# connections_to_beaglebone.net
KiCad netlist of a schematic drawn in Altium Designer
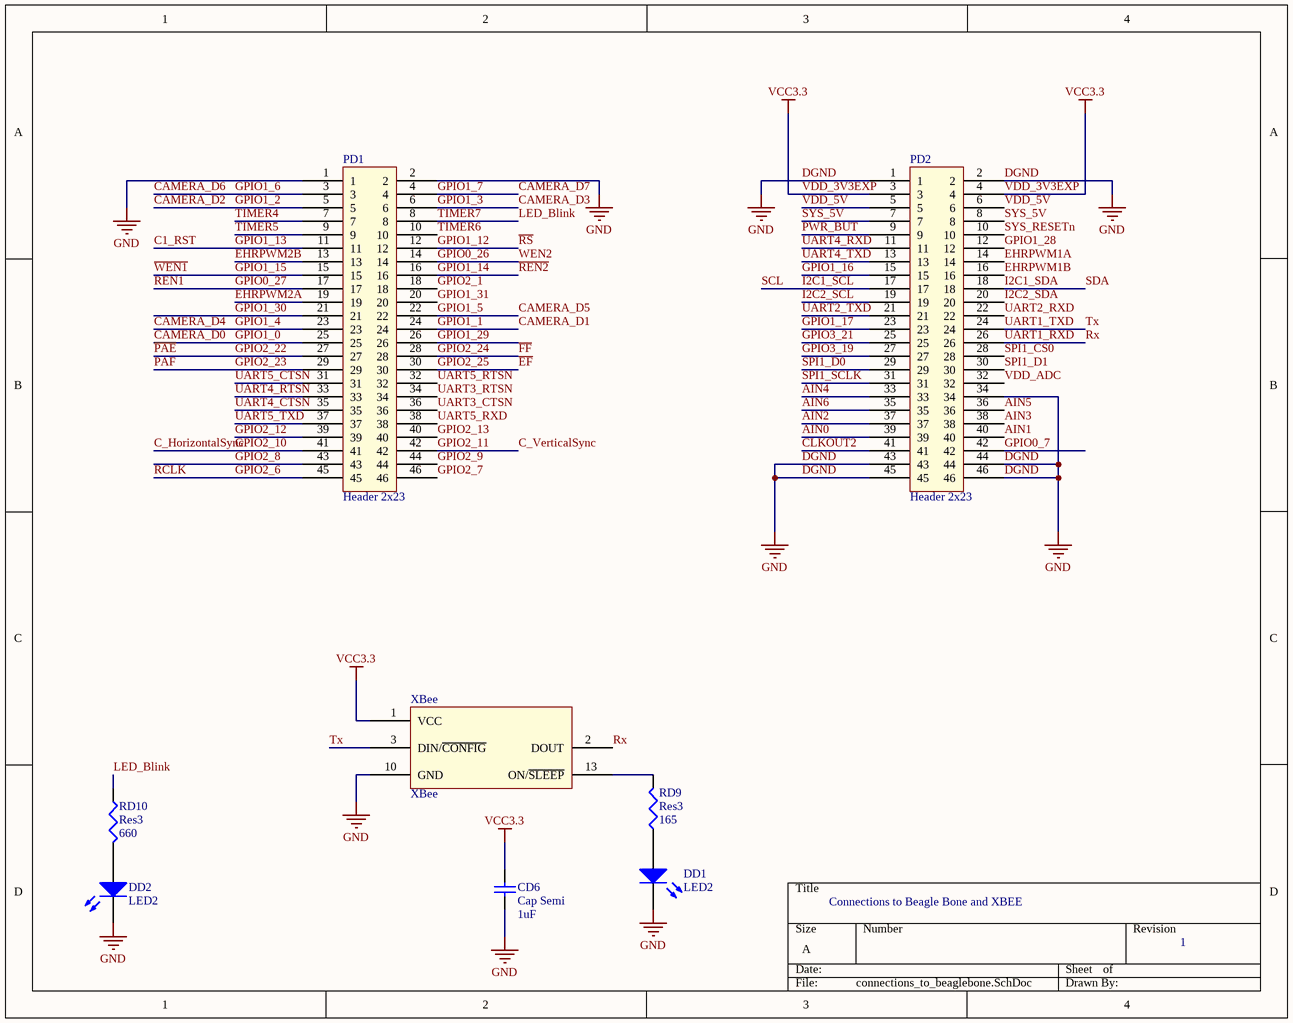
[diagram p0: connections_to_beaglebone.SchDoc]

(export (version "E")
  (design (tool "Eeschema 10.0.6"))
  (components
    (comp (ref "CD6")
      (value "Cap Semi")
      (footprint "CAPC1608L")
      (description "Capacitor (Semiconductor SIM Model)")
      (fields (field (name "ALTIUM_VALUE") "1uF") (field (name "PUBLISHER") "Altium Limited"))
      (libsource (lib "Miscellaneous Devices") (part "Cap Semi"))
    )
    (comp (ref "DD1")
      (value "LED2")
      (footprint "DIODE1608")
      (description "Typical RED, GREEN, YELLOW, AMBER GaAs LED")
      (fields (field (name "PUBLISHER") "Altium Limited"))
      (libsource (lib "") (part "LED2_1"))
    )
    (comp (ref "DD2")
      (value "LED2")
      (footprint "DIODE1608")
      (description "Typical RED, GREEN, YELLOW, AMBER GaAs LED")
      (fields (field (name "PUBLISHER") "Altium Limited"))
      (libsource (lib "Miscellaneous Devices") (part "LED2"))
    )
    (comp (ref "PD1")
      (value "Header 2x23")
      (footprint "HDR2X23")
      (libsource (lib "daughterboard") (part "Header 2x23"))
    )
    (comp (ref "PD2")
      (value "Header 2x23")
      (footprint "HDR2X23")
      (libsource (lib "daughterboard") (part "Header 2x23"))
    )
    (comp (ref "RD9")
      (value "Res3")
      (footprint "RESC1608L")
      (description "Resistor")
      (fields (field (name "ALTIUM_VALUE") "165") (field (name "PUBLISHER") "Altium Limited"))
      (libsource (lib "") (part "Res3_1"))
    )
    (comp (ref "RD10")
      (value "Res3")
      (footprint "RESC1608L")
      (description "Resistor")
      (fields (field (name "ALTIUM_VALUE") "660") (field (name "PUBLISHER") "Altium Limited"))
      (libsource (lib "Miscellaneous Devices") (part "Res3"))
    )
    (comp (ref "XBee")
      (value "XBee")
      (footprint "XBee")
      (description "XBee wireless transmitter/reveiver")
      (libsource (lib "daughterboard") (part "XBee"))
    )
  )
  (nets
    (net (code "1") (name "/AIN0") (class "Default")
      (node (ref "PD2") (pin "39") (pinfunction "39_39") (pintype "passive"))
    )
    (net (code "2") (name "/AIN1") (class "Default")
      (node (ref "PD2") (pin "40") (pinfunction "40_40") (pintype "passive"))
    )
    (net (code "3") (name "/AIN2") (class "Default")
      (node (ref "PD2") (pin "37") (pinfunction "37_37") (pintype "passive"))
    )
    (net (code "4") (name "/AIN3") (class "Default")
      (node (ref "PD2") (pin "38") (pinfunction "38_38") (pintype "passive"))
    )
    (net (code "5") (name "/AIN4") (class "Default")
      (node (ref "PD2") (pin "33") (pinfunction "33_33") (pintype "passive"))
    )
    (net (code "6") (name "/AIN5") (class "Default")
      (node (ref "PD2") (pin "36") (pinfunction "36_36") (pintype "passive"))
    )
    (net (code "7") (name "/AIN6") (class "Default")
      (node (ref "PD2") (pin "35") (pinfunction "35_35") (pintype "passive"))
    )
    (net (code "8") (name "/C1_RST") (class "Default")
      (node (ref "PD1") (pin "11") (pinfunction "11_11") (pintype "passive"))
    )
    (net (code "9") (name "/CAMERA_D0") (class "Default")
      (node (ref "PD1") (pin "25") (pinfunction "25_25") (pintype "passive"))
    )
    (net (code "10") (name "/CAMERA_D1") (class "Default")
      (node (ref "PD1") (pin "24") (pinfunction "24_24") (pintype "passive"))
    )
    (net (code "11") (name "/CAMERA_D2") (class "Default")
      (node (ref "PD1") (pin "5") (pinfunction "5_5") (pintype "passive"))
    )
    (net (code "12") (name "/CAMERA_D3") (class "Default")
      (node (ref "PD1") (pin "6") (pinfunction "6_6") (pintype "passive"))
    )
    (net (code "13") (name "/CAMERA_D4") (class "Default")
      (node (ref "PD1") (pin "23") (pinfunction "23_23") (pintype "passive"))
    )
    (net (code "14") (name "/CAMERA_D5") (class "Default")
      (node (ref "PD1") (pin "22") (pinfunction "22_22") (pintype "passive"))
    )
    (net (code "15") (name "/CAMERA_D6") (class "Default")
      (node (ref "PD1") (pin "3") (pinfunction "3_3") (pintype "passive"))
    )
    (net (code "16") (name "/CAMERA_D7") (class "Default")
      (node (ref "PD1") (pin "4") (pinfunction "4_4") (pintype "passive"))
    )
    (net (code "17") (name "/CLKOUT2") (class "Default")
      (node (ref "PD2") (pin "41") (pinfunction "41_41") (pintype "passive"))
    )
    (net (code "18") (name "/C_HorizontalSync") (class "Default")
      (node (ref "PD1") (pin "41") (pinfunction "41_41") (pintype "passive"))
    )
    (net (code "19") (name "/C_VerticalSync") (class "Default")
      (node (ref "PD1") (pin "42") (pinfunction "42_42") (pintype "passive"))
    )
    (net (code "20") (name "/EHRPWM1A") (class "Default")
      (node (ref "PD2") (pin "14") (pinfunction "14_14") (pintype "passive"))
    )
    (net (code "21") (name "/EHRPWM1B") (class "Default")
      (node (ref "PD2") (pin "16") (pinfunction "16_16") (pintype "passive"))
    )
    (net (code "22") (name "/EHRPWM2A") (class "Default")
      (node (ref "PD1") (pin "19") (pinfunction "19_19") (pintype "passive"))
    )
    (net (code "23") (name "/EHRPWM2B") (class "Default")
      (node (ref "PD1") (pin "13") (pinfunction "13_13") (pintype "passive"))
    )
    (net (code "24") (name "/GPIO0_7") (class "Default")
      (node (ref "PD2") (pin "42") (pinfunction "42_42") (pintype "passive"))
    )
    (net (code "25") (name "/GPIO0_26") (class "Default")
      (node (ref "PD1") (pin "14") (pinfunction "14_14") (pintype "passive"))
    )
    (net (code "26") (name "/GPIO0_27") (class "Default")
      (node (ref "PD1") (pin "17") (pinfunction "17_17") (pintype "passive"))
    )
    (net (code "27") (name "/GPIO1_12") (class "Default")
      (node (ref "PD1") (pin "12") (pinfunction "12_12") (pintype "passive"))
    )
    (net (code "28") (name "/GPIO1_14") (class "Default")
      (node (ref "PD1") (pin "16") (pinfunction "16_16") (pintype "passive"))
    )
    (net (code "29") (name "/GPIO1_15") (class "Default")
      (node (ref "PD1") (pin "15") (pinfunction "15_15") (pintype "passive"))
    )
    (net (code "30") (name "/GPIO1_16") (class "Default")
      (node (ref "PD2") (pin "15") (pinfunction "15_15") (pintype "passive"))
    )
    (net (code "31") (name "/GPIO1_17") (class "Default")
      (node (ref "PD2") (pin "23") (pinfunction "23_23") (pintype "passive"))
    )
    (net (code "32") (name "/GPIO1_28") (class "Default")
      (node (ref "PD2") (pin "12") (pinfunction "12_12") (pintype "passive"))
    )
    (net (code "33") (name "/GPIO1_29") (class "Default")
      (node (ref "PD1") (pin "26") (pinfunction "26_26") (pintype "passive"))
    )
    (net (code "34") (name "/GPIO1_30") (class "Default")
      (node (ref "PD1") (pin "21") (pinfunction "21_21") (pintype "passive"))
    )
    (net (code "35") (name "/GPIO1_31") (class "Default")
      (node (ref "PD1") (pin "20") (pinfunction "20_20") (pintype "passive"))
    )
    (net (code "36") (name "/GPIO2_1") (class "Default")
      (node (ref "PD1") (pin "18") (pinfunction "18_18") (pintype "passive"))
    )
    (net (code "37") (name "/GPIO2_6") (class "Default")
      (node (ref "PD1") (pin "45") (pinfunction "45_45") (pintype "passive"))
    )
    (net (code "38") (name "/GPIO2_7") (class "Default")
      (node (ref "PD1") (pin "46") (pinfunction "46_46") (pintype "passive"))
    )
    (net (code "39") (name "/GPIO2_8") (class "Default")
      (node (ref "PD1") (pin "43") (pinfunction "43_43") (pintype "passive"))
    )
    (net (code "40") (name "/GPIO2_9") (class "Default")
      (node (ref "PD1") (pin "44") (pinfunction "44_44") (pintype "passive"))
    )
    (net (code "41") (name "/GPIO2_12") (class "Default")
      (node (ref "PD1") (pin "39") (pinfunction "39_39") (pintype "passive"))
    )
    (net (code "42") (name "/GPIO2_13") (class "Default")
      (node (ref "PD1") (pin "40") (pinfunction "40_40") (pintype "passive"))
    )
    (net (code "43") (name "/GPIO2_22") (class "Default")
      (node (ref "PD1") (pin "27") (pinfunction "27_27") (pintype "passive"))
    )
    (net (code "44") (name "/GPIO2_23") (class "Default")
      (node (ref "PD1") (pin "29") (pinfunction "29_29") (pintype "passive"))
    )
    (net (code "45") (name "/GPIO2_24") (class "Default")
      (node (ref "PD1") (pin "28") (pinfunction "28_28") (pintype "passive"))
    )
    (net (code "46") (name "/GPIO2_25") (class "Default")
      (node (ref "PD1") (pin "30") (pinfunction "30_30") (pintype "passive"))
    )
    (net (code "47") (name "/GPIO3_19") (class "Default")
      (node (ref "PD2") (pin "27") (pinfunction "27_27") (pintype "passive"))
    )
    (net (code "48") (name "/GPIO3_21") (class "Default")
      (node (ref "PD2") (pin "25") (pinfunction "25_25") (pintype "passive"))
    )
    (net (code "49") (name "/I2C1_SCL") (class "Default")
      (node (ref "PD2") (pin "17") (pinfunction "17_17") (pintype "passive"))
    )
    (net (code "50") (name "/I2C1_SDA") (class "Default")
      (node (ref "PD2") (pin "18") (pinfunction "18_18") (pintype "passive"))
    )
    (net (code "51") (name "/I2C2_SCL") (class "Default")
      (node (ref "PD2") (pin "19") (pinfunction "19_19") (pintype "passive"))
    )
    (net (code "52") (name "/I2C2_SDA") (class "Default")
      (node (ref "PD2") (pin "20") (pinfunction "20_20") (pintype "passive"))
    )
    (net (code "53") (name "/LED_Blink") (class "Default")
      (node (ref "PD1") (pin "8") (pinfunction "8_8") (pintype "passive"))
      (node (ref "RD10") (pin "2") (pinfunction "2_2") (pintype "passive"))
    )
    (net (code "54") (name "/PWR_BUT") (class "Default")
      (node (ref "PD2") (pin "9") (pinfunction "9_9") (pintype "passive"))
    )
    (net (code "55") (name "/Rx") (class "Default")
      (node (ref "PD2") (pin "26") (pinfunction "26_26") (pintype "passive"))
      (node (ref "XBee") (pin "2") (pinfunction "DOUT_2") (pintype "passive"))
    )
    (net (code "56") (name "/SPI1_CS0") (class "Default")
      (node (ref "PD2") (pin "28") (pinfunction "28_28") (pintype "passive"))
    )
    (net (code "57") (name "/SPI1_D0") (class "Default")
      (node (ref "PD2") (pin "29") (pinfunction "29_29") (pintype "passive"))
    )
    (net (code "58") (name "/SPI1_D1") (class "Default")
      (node (ref "PD2") (pin "30") (pinfunction "30_30") (pintype "passive"))
    )
    (net (code "59") (name "/SPI1_SCLK") (class "Default")
      (node (ref "PD2") (pin "31") (pinfunction "31_31") (pintype "passive"))
    )
    (net (code "60") (name "/SYS_5V") (class "Default")
      (node (ref "PD2") (pin "7") (pinfunction "7_7") (pintype "passive"))
      (node (ref "PD2") (pin "8") (pinfunction "8_8") (pintype "passive"))
    )
    (net (code "61") (name "/SYS_RESETn") (class "Default")
      (node (ref "PD2") (pin "10") (pinfunction "10_10") (pintype "passive"))
    )
    (net (code "62") (name "/TIMER4") (class "Default")
      (node (ref "PD1") (pin "7") (pinfunction "7_7") (pintype "passive"))
    )
    (net (code "63") (name "/TIMER5") (class "Default")
      (node (ref "PD1") (pin "9") (pinfunction "9_9") (pintype "passive"))
    )
    (net (code "64") (name "/TIMER6") (class "Default")
      (node (ref "PD1") (pin "10") (pinfunction "10_10") (pintype "passive"))
    )
    (net (code "65") (name "/Tx") (class "Default")
      (node (ref "PD2") (pin "24") (pinfunction "24_24") (pintype "passive"))
      (node (ref "XBee") (pin "3") (pinfunction "DIN/~{CONFIG}_3") (pintype "passive"))
    )
    (net (code "66") (name "/UART2_RXD") (class "Default")
      (node (ref "PD2") (pin "22") (pinfunction "22_22") (pintype "passive"))
    )
    (net (code "67") (name "/UART2_TXD") (class "Default")
      (node (ref "PD2") (pin "21") (pinfunction "21_21") (pintype "passive"))
    )
    (net (code "68") (name "/UART3_CTSN") (class "Default")
      (node (ref "PD1") (pin "36") (pinfunction "36_36") (pintype "passive"))
    )
    (net (code "69") (name "/UART3_RTSN") (class "Default")
      (node (ref "PD1") (pin "34") (pinfunction "34_34") (pintype "passive"))
    )
    (net (code "70") (name "/UART4_CTSN") (class "Default")
      (node (ref "PD1") (pin "35") (pinfunction "35_35") (pintype "passive"))
    )
    (net (code "71") (name "/UART4_RTSN") (class "Default")
      (node (ref "PD1") (pin "33") (pinfunction "33_33") (pintype "passive"))
    )
    (net (code "72") (name "/UART4_RXD") (class "Default")
      (node (ref "PD2") (pin "11") (pinfunction "11_11") (pintype "passive"))
    )
    (net (code "73") (name "/UART4_TXD") (class "Default")
      (node (ref "PD2") (pin "13") (pinfunction "13_13") (pintype "passive"))
    )
    (net (code "74") (name "/UART5_CTSN") (class "Default")
      (node (ref "PD1") (pin "31") (pinfunction "31_31") (pintype "passive"))
    )
    (net (code "75") (name "/UART5_RTSN") (class "Default")
      (node (ref "PD1") (pin "32") (pinfunction "32_32") (pintype "passive"))
    )
    (net (code "76") (name "/UART5_RXD") (class "Default")
      (node (ref "PD1") (pin "38") (pinfunction "38_38") (pintype "passive"))
    )
    (net (code "77") (name "/UART5_TXD") (class "Default")
      (node (ref "PD1") (pin "37") (pinfunction "37_37") (pintype "passive"))
    )
    (net (code "78") (name "/VDD_5V") (class "Default")
      (node (ref "PD2") (pin "5") (pinfunction "5_5") (pintype "passive"))
      (node (ref "PD2") (pin "6") (pinfunction "6_6") (pintype "passive"))
    )
    (net (code "79") (name "/VDD_ADC") (class "Default")
      (node (ref "PD2") (pin "32") (pinfunction "32_32") (pintype "passive"))
    )
    (net (code "80") (name "GND") (class "Default")
      (node (ref "CD6") (pin "1") (pinfunction "1_1") (pintype "passive"))
      (node (ref "DD1") (pin "2") (pinfunction "K_2") (pintype "passive"))
      (node (ref "DD2") (pin "2") (pinfunction "K_2") (pintype "passive"))
      (node (ref "PD1") (pin "1") (pinfunction "1_1") (pintype "passive"))
      (node (ref "PD1") (pin "2") (pinfunction "2_2") (pintype "passive"))
      (node (ref "PD2") (pin "1") (pinfunction "1_1") (pintype "passive"))
      (node (ref "PD2") (pin "2") (pinfunction "2_2") (pintype "passive"))
      (node (ref "PD2") (pin "34") (pinfunction "34_34") (pintype "passive"))
      (node (ref "PD2") (pin "43") (pinfunction "43_43") (pintype "passive"))
      (node (ref "PD2") (pin "44") (pinfunction "44_44") (pintype "passive"))
      (node (ref "PD2") (pin "45") (pinfunction "45_45") (pintype "passive"))
      (node (ref "PD2") (pin "46") (pinfunction "46_46") (pintype "passive"))
      (node (ref "XBee") (pin "10") (pinfunction "GND_10") (pintype "passive"))
    )
    (net (code "81") (name "Net-(DD1-A)") (class "Default")
      (node (ref "DD1") (pin "1") (pinfunction "A_1") (pintype "passive"))
      (node (ref "RD9") (pin "1") (pinfunction "1_1") (pintype "passive"))
    )
    (net (code "82") (name "Net-(DD2-A)") (class "Default")
      (node (ref "DD2") (pin "1") (pinfunction "A_1") (pintype "passive"))
      (node (ref "RD10") (pin "1") (pinfunction "1_1") (pintype "passive"))
    )
    (net (code "83") (name "Net-(XBee-ON{slash}~{SLEEP})") (class "Default")
      (node (ref "RD9") (pin "2") (pinfunction "2_2") (pintype "passive"))
      (node (ref "XBee") (pin "13") (pinfunction "ON/~{SLEEP}_13") (pintype "passive"))
    )
    (net (code "84") (name "VCC3.3") (class "Default")
      (node (ref "CD6") (pin "2") (pinfunction "2_2") (pintype "passive"))
      (node (ref "PD2") (pin "3") (pinfunction "3_3") (pintype "passive"))
      (node (ref "PD2") (pin "4") (pinfunction "4_4") (pintype "passive"))
      (node (ref "XBee") (pin "1") (pinfunction "VCC_1") (pintype "passive"))
    )
    (net (code "85") (name "unconnected-(XBee-AD0{slash}DIO0-Pad20)") (class "Default")
      (node (ref "XBee") (pin "20") (pinfunction "AD0/DIO0_20") (pintype "passive"))
    )
    (net (code "86") (name "unconnected-(XBee-AD1{slash}DIO1-Pad19)") (class "Default")
      (node (ref "XBee") (pin "19") (pinfunction "AD1/DIO1_19") (pintype "passive"))
    )
    (net (code "87") (name "unconnected-(XBee-AD2{slash}DIO2-Pad18)") (class "Default")
      (node (ref "XBee") (pin "18") (pinfunction "AD2/DIO2_18") (pintype "passive"))
    )
    (net (code "88") (name "unconnected-(XBee-AD3{slash}DIO3-Pad17)") (class "Default")
      (node (ref "XBee") (pin "17") (pinfunction "AD3/DIO3_17") (pintype "passive"))
    )
    (net (code "89") (name "unconnected-(XBee-AD4{slash}DIO4-Pad11)") (class "Default")
      (node (ref "XBee") (pin "11") (pinfunction "AD4/DIO4_11") (pintype "passive"))
    )
    (net (code "90") (name "unconnected-(XBee-Associate{slash}AD5{slash}DIO5-Pad15)") (class "Default")
      (node (ref "XBee") (pin "15") (pinfunction "Associate/AD5/DIO5_15") (pintype "passive"))
    )
    (net (code "91") (name "unconnected-(XBee-D08-Pad4)") (class "Default")
      (node (ref "XBee") (pin "4") (pinfunction "D08_4") (pintype "passive"))
    )
    (net (code "92") (name "unconnected-(XBee-PWM0{slash}RSSI-Pad6)") (class "Default")
      (node (ref "XBee") (pin "6") (pinfunction "PWM0/RSSI_6") (pintype "passive"))
    )
    (net (code "93") (name "unconnected-(XBee-PWM1-Pad7)") (class "Default")
      (node (ref "XBee") (pin "7") (pinfunction "PWM1_7") (pintype "passive"))
    )
    (net (code "94") (name "unconnected-(XBee-VREF-Pad14)") (class "Default")
      (node (ref "XBee") (pin "14") (pinfunction "VREF_14") (pintype "passive"))
    )
    (net (code "95") (name "unconnected-(XBee-[reserved]-Pad8)") (class "Default")
      (node (ref "XBee") (pin "8") (pinfunction "[reserved]_8") (pintype "passive"))
    )
    (net (code "96") (name "unconnected-(XBee-~{CTS}{slash}DIO7-Pad12)") (class "Default")
      (node (ref "XBee") (pin "12") (pinfunction "~{CTS}/DIO7_12") (pintype "passive"))
    )
    (net (code "97") (name "unconnected-(XBee-~{DTR}{slash}SLEEP_RQ{slash}DI8-Pad9)") (class "Default")
      (node (ref "XBee") (pin "9") (pinfunction "~{DTR}/SLEEP_RQ/DI8_9") (pintype "passive"))
    )
    (net (code "98") (name "unconnected-(XBee-~{RESET}-Pad5)") (class "Default")
      (node (ref "XBee") (pin "5") (pinfunction "~{RESET}_5") (pintype "passive"))
    )
    (net (code "99") (name "unconnected-(XBee-~{RTS}{slash}AD6{slash}DIO6-Pad16)") (class "Default")
      (node (ref "XBee") (pin "16") (pinfunction "~{RTS}/AD6/DIO6_16") (pintype "passive"))
    )
  )
)
